# SCH_laptrinhoto_2025-12-04.net
KiCad netlist of a schematic drawn in EasyEDA
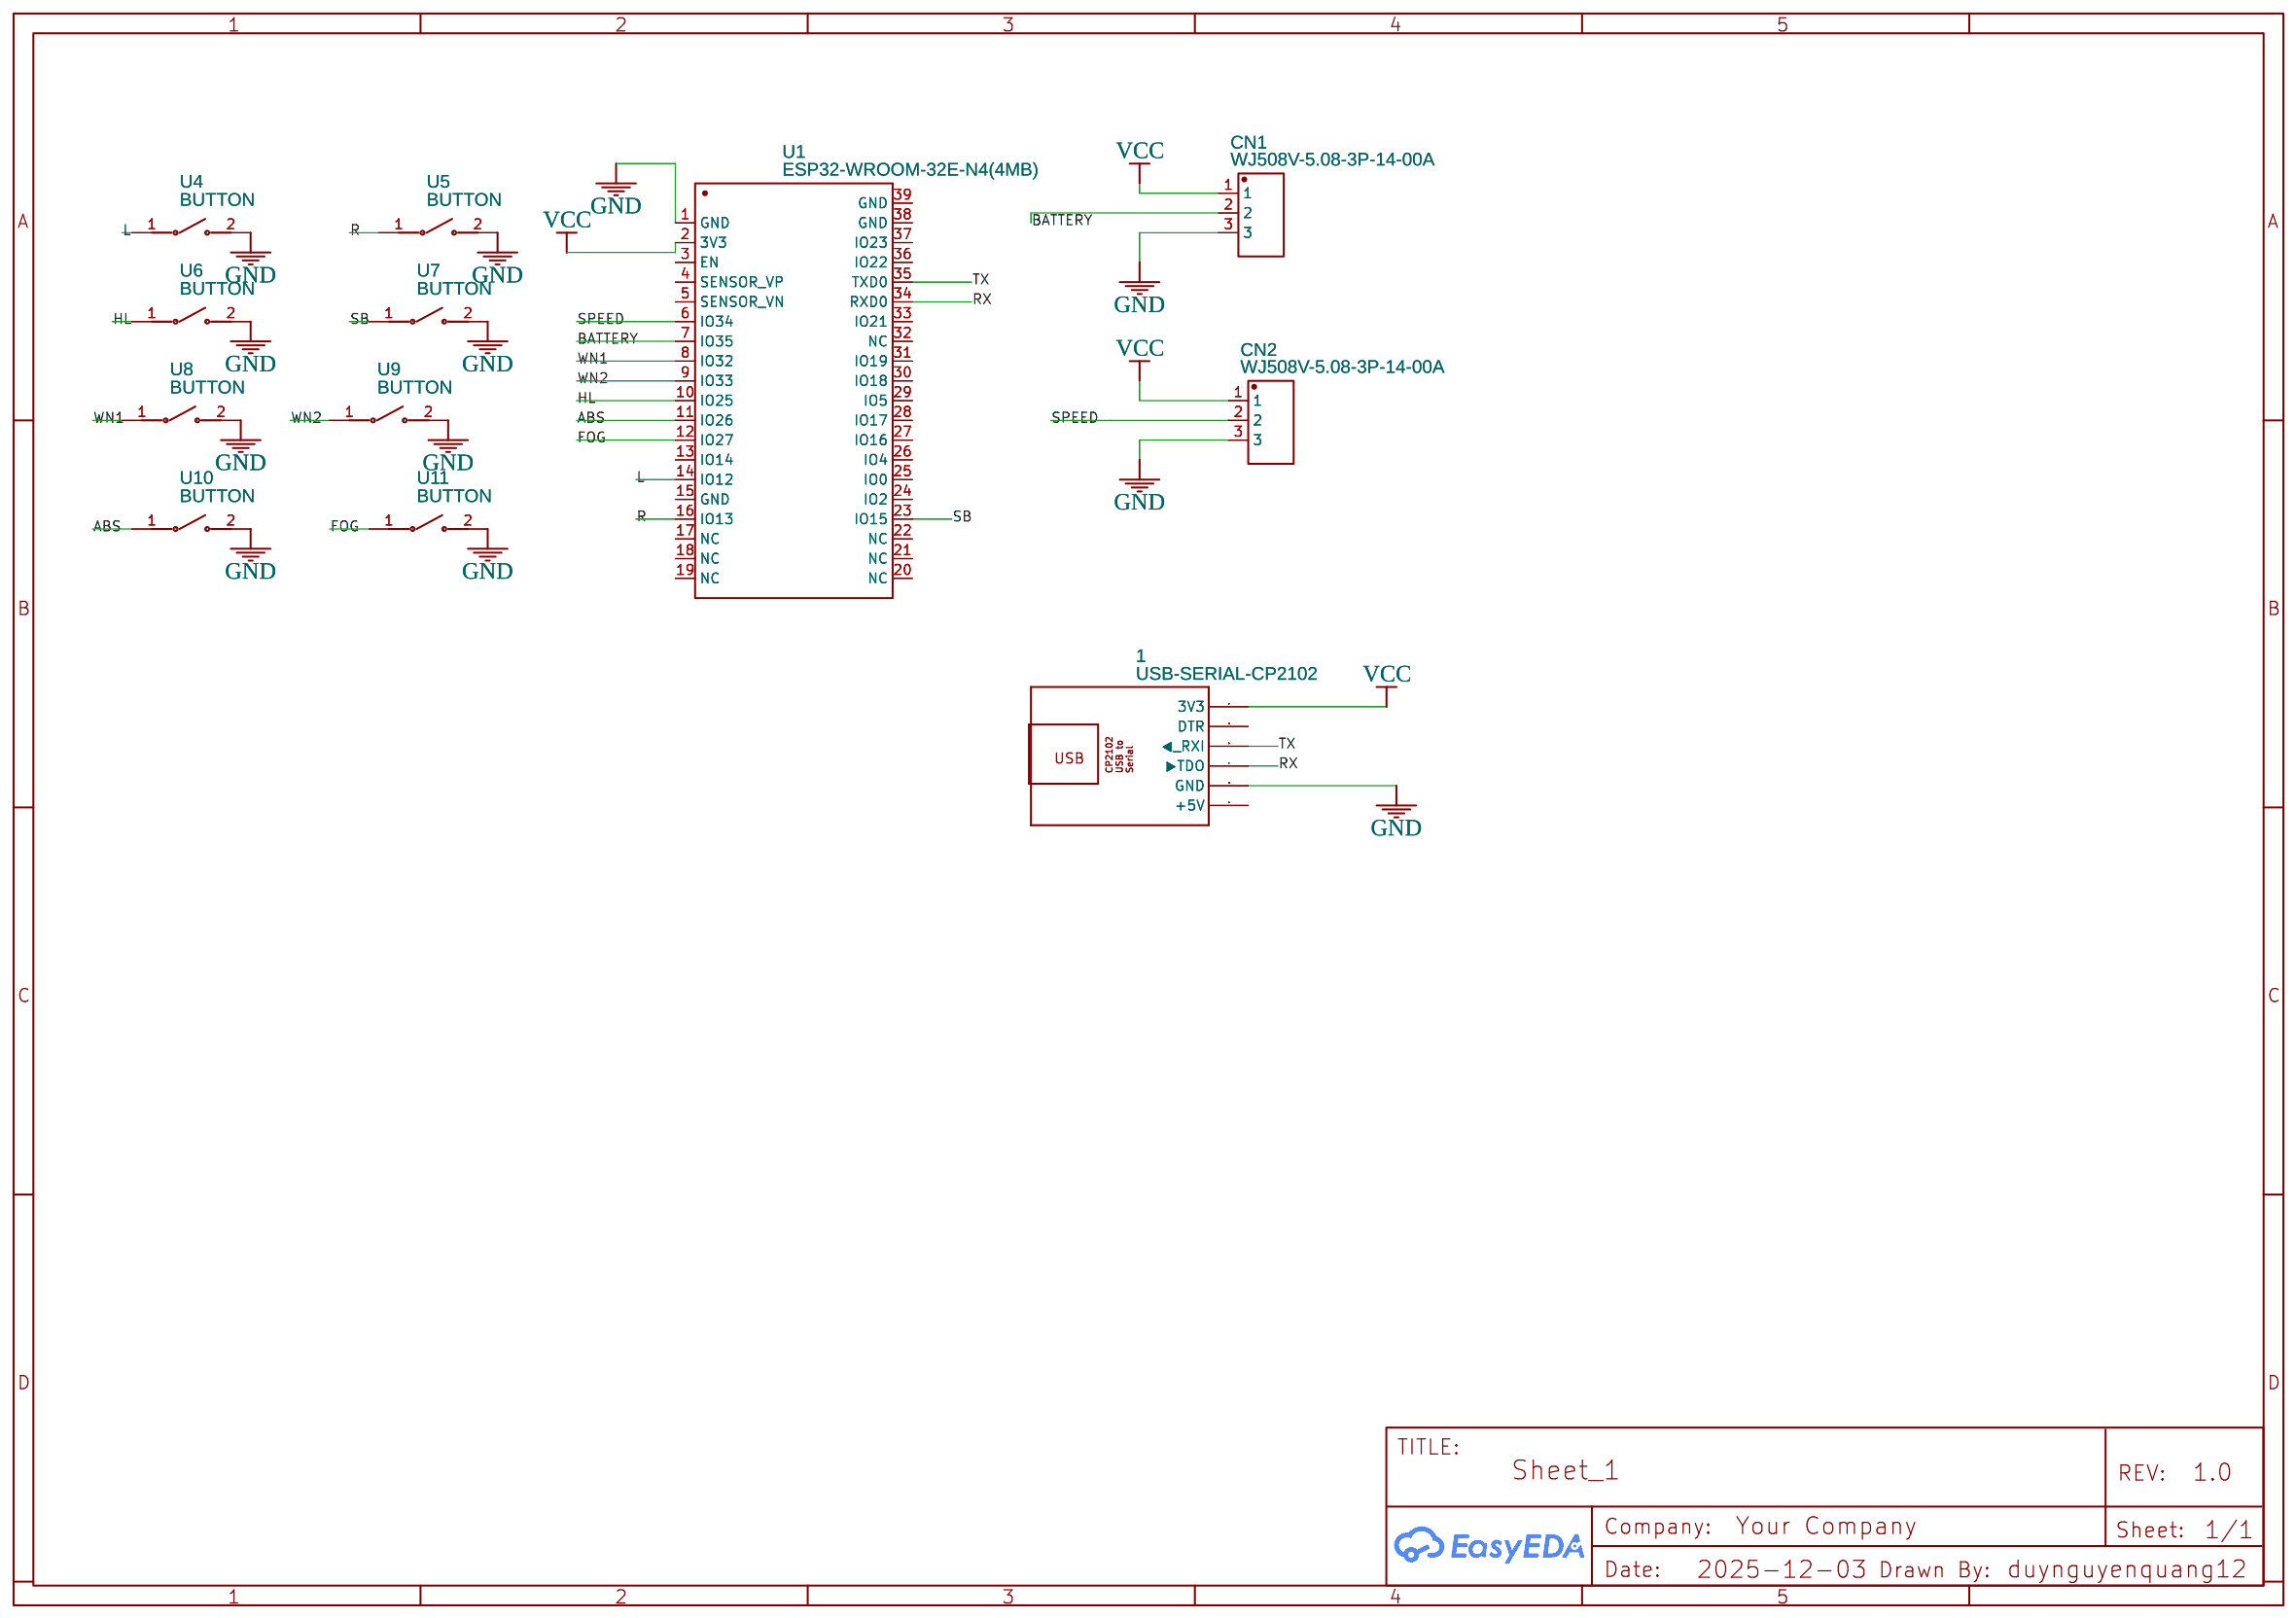
[diagram p0: schematic sheet]

(export (version "E")
  (design (tool "Eeschema 10.0.6"))
  (components
    (comp (ref "1") (value "USB-SERIAL-CP2102") (libsource (lib "") (part "USB-SERIAL-CP2102")))
    (comp (ref "CN1")
      (value "WJ508V-5.08-3P-14-00A")
      (fields (field (name "Manufacturer") "ReliaPro"))
      (libsource (lib "") (part "WJ508V-5.08-3P-14-00A"))
    )
    (comp (ref "CN2")
      (value "WJ508V-5.08-3P-14-00A")
      (fields (field (name "Manufacturer") "ReliaPro"))
      (libsource (lib "") (part "WJ508V-5.08-3P-14-00A"))
    )
    (comp (ref "U1") (value "ESP32-WROOM-32E-N4(4MB)") (libsource (lib "") (part "ESP32-WROOM-32E-N4(4MB)")))
    (comp (ref "U4") (value "BUTTON") (libsource (lib "") (part "BUTTON")))
    (comp (ref "U5") (value "BUTTON") (libsource (lib "") (part "BUTTON")))
    (comp (ref "U6") (value "BUTTON") (libsource (lib "") (part "BUTTON")))
    (comp (ref "U7") (value "BUTTON") (libsource (lib "") (part "BUTTON")))
    (comp (ref "U8") (value "BUTTON") (libsource (lib "") (part "BUTTON")))
    (comp (ref "U9") (value "BUTTON") (libsource (lib "") (part "BUTTON")))
    (comp (ref "U10") (value "BUTTON") (libsource (lib "") (part "BUTTON")))
    (comp (ref "U11") (value "BUTTON") (libsource (lib "") (part "BUTTON")))
  )
  (nets
    (net (code "1") (name "/ABS") (class "Default")
      (node (ref "U1") (pin "11") (pinfunction "IO26_11") (pintype "unspecified"))
      (node (ref "U10") (pin "1") (pinfunction "1_1") (pintype "unspecified"))
    )
    (net (code "2") (name "/BATTERY") (class "Default")
      (node (ref "CN1") (pin "2") (pinfunction "2_2") (pintype "unspecified"))
      (node (ref "U1") (pin "7") (pinfunction "IO35_7") (pintype "unspecified"))
    )
    (net (code "3") (name "/FOG") (class "Default")
      (node (ref "U1") (pin "12") (pinfunction "IO27_12") (pintype "unspecified"))
      (node (ref "U11") (pin "1") (pinfunction "1_1") (pintype "unspecified"))
    )
    (net (code "4") (name "/HL") (class "Default")
      (node (ref "U1") (pin "10") (pinfunction "IO25_10") (pintype "unspecified"))
      (node (ref "U6") (pin "1") (pinfunction "1_1") (pintype "unspecified"))
    )
    (net (code "5") (name "/L") (class "Default")
      (node (ref "U1") (pin "14") (pinfunction "IO12_14") (pintype "unspecified"))
      (node (ref "U4") (pin "1") (pinfunction "1_1") (pintype "unspecified"))
    )
    (net (code "6") (name "/R") (class "Default")
      (node (ref "U1") (pin "16") (pinfunction "IO13_16") (pintype "unspecified"))
      (node (ref "U5") (pin "1") (pinfunction "1_1") (pintype "unspecified"))
    )
    (net (code "7") (name "/RX") (class "Default")
      (node (ref "1") (pin "4") (pinfunction "▶TDO_4") (pintype "bidirectional"))
      (node (ref "U1") (pin "34") (pinfunction "RXD0_34") (pintype "unspecified"))
    )
    (net (code "8") (name "/SB") (class "Default")
      (node (ref "U1") (pin "23") (pinfunction "IO15_23") (pintype "unspecified"))
      (node (ref "U7") (pin "1") (pinfunction "1_1") (pintype "unspecified"))
    )
    (net (code "9") (name "/SPEED") (class "Default")
      (node (ref "CN2") (pin "2") (pinfunction "2_2") (pintype "unspecified"))
      (node (ref "U1") (pin "6") (pinfunction "IO34_6") (pintype "unspecified"))
    )
    (net (code "10") (name "/TX") (class "Default")
      (node (ref "1") (pin "3") (pinfunction "◀_RXI_3") (pintype "bidirectional"))
      (node (ref "U1") (pin "35") (pinfunction "TXD0_35") (pintype "unspecified"))
    )
    (net (code "11") (name "/WN1") (class "Default")
      (node (ref "U1") (pin "8") (pinfunction "IO32_8") (pintype "unspecified"))
      (node (ref "U8") (pin "1") (pinfunction "1_1") (pintype "unspecified"))
    )
    (net (code "12") (name "/WN2") (class "Default")
      (node (ref "U1") (pin "9") (pinfunction "IO33_9") (pintype "unspecified"))
      (node (ref "U9") (pin "1") (pinfunction "1_1") (pintype "unspecified"))
    )
    (net (code "13") (name "GND") (class "Default")
      (node (ref "1") (pin "5") (pinfunction "GND_5") (pintype "bidirectional"))
      (node (ref "CN1") (pin "3") (pinfunction "3_3") (pintype "unspecified"))
      (node (ref "CN2") (pin "3") (pinfunction "3_3") (pintype "unspecified"))
      (node (ref "U1") (pin "1") (pinfunction "GND_1") (pintype "unspecified"))
      (node (ref "U10") (pin "2") (pinfunction "2_2") (pintype "unspecified"))
      (node (ref "U11") (pin "2") (pinfunction "2_2") (pintype "unspecified"))
      (node (ref "U4") (pin "2") (pinfunction "2_2") (pintype "unspecified"))
      (node (ref "U5") (pin "2") (pinfunction "2_2") (pintype "unspecified"))
      (node (ref "U6") (pin "2") (pinfunction "2_2") (pintype "unspecified"))
      (node (ref "U7") (pin "2") (pinfunction "2_2") (pintype "unspecified"))
      (node (ref "U8") (pin "2") (pinfunction "2_2") (pintype "unspecified"))
      (node (ref "U9") (pin "2") (pinfunction "2_2") (pintype "unspecified"))
    )
    (net (code "14") (name "VCC") (class "Default")
      (node (ref "1") (pin "1") (pinfunction "3V3_1") (pintype "bidirectional"))
      (node (ref "CN1") (pin "1") (pinfunction "1_1") (pintype "unspecified"))
      (node (ref "CN2") (pin "1") (pinfunction "1_1") (pintype "unspecified"))
      (node (ref "U1") (pin "2") (pinfunction "3V3_2") (pintype "unspecified"))
    )
    (net (code "15") (name "unconnected-(1-+5V-Pad6)") (class "Default")
      (node (ref "1") (pin "6") (pinfunction "+5V_6") (pintype "bidirectional"))
    )
    (net (code "16") (name "unconnected-(1-DTR-Pad2)") (class "Default")
      (node (ref "1") (pin "2") (pinfunction "DTR_2") (pintype "bidirectional"))
    )
    (net (code "17") (name "unconnected-(U1-EN-Pad3)") (class "Default")
      (node (ref "U1") (pin "3") (pinfunction "EN_3") (pintype "unspecified"))
    )
    (net (code "18") (name "unconnected-(U1-GND-Pad15)") (class "Default")
      (node (ref "U1") (pin "15") (pinfunction "GND_15") (pintype "unspecified"))
    )
    (net (code "19") (name "unconnected-(U1-GND-Pad38)") (class "Default")
      (node (ref "U1") (pin "38") (pinfunction "GND_38") (pintype "unspecified"))
    )
    (net (code "20") (name "unconnected-(U1-GND-Pad39)") (class "Default")
      (node (ref "U1") (pin "39") (pinfunction "GND_39") (pintype "unspecified"))
    )
    (net (code "21") (name "unconnected-(U1-IO0-Pad25)") (class "Default")
      (node (ref "U1") (pin "25") (pinfunction "IO0_25") (pintype "unspecified"))
    )
    (net (code "22") (name "unconnected-(U1-IO2-Pad24)") (class "Default")
      (node (ref "U1") (pin "24") (pinfunction "IO2_24") (pintype "unspecified"))
    )
    (net (code "23") (name "unconnected-(U1-IO4-Pad26)") (class "Default")
      (node (ref "U1") (pin "26") (pinfunction "IO4_26") (pintype "unspecified"))
    )
    (net (code "24") (name "unconnected-(U1-IO5-Pad29)") (class "Default")
      (node (ref "U1") (pin "29") (pinfunction "IO5_29") (pintype "unspecified"))
    )
    (net (code "25") (name "unconnected-(U1-IO14-Pad13)") (class "Default")
      (node (ref "U1") (pin "13") (pinfunction "IO14_13") (pintype "unspecified"))
    )
    (net (code "26") (name "unconnected-(U1-IO16-Pad27)") (class "Default")
      (node (ref "U1") (pin "27") (pinfunction "IO16_27") (pintype "unspecified"))
    )
    (net (code "27") (name "unconnected-(U1-IO17-Pad28)") (class "Default")
      (node (ref "U1") (pin "28") (pinfunction "IO17_28") (pintype "unspecified"))
    )
    (net (code "28") (name "unconnected-(U1-IO18-Pad30)") (class "Default")
      (node (ref "U1") (pin "30") (pinfunction "IO18_30") (pintype "unspecified"))
    )
    (net (code "29") (name "unconnected-(U1-IO19-Pad31)") (class "Default")
      (node (ref "U1") (pin "31") (pinfunction "IO19_31") (pintype "unspecified"))
    )
    (net (code "30") (name "unconnected-(U1-IO21-Pad33)") (class "Default")
      (node (ref "U1") (pin "33") (pinfunction "IO21_33") (pintype "unspecified"))
    )
    (net (code "31") (name "unconnected-(U1-IO22-Pad36)") (class "Default")
      (node (ref "U1") (pin "36") (pinfunction "IO22_36") (pintype "unspecified"))
    )
    (net (code "32") (name "unconnected-(U1-IO23-Pad37)") (class "Default")
      (node (ref "U1") (pin "37") (pinfunction "IO23_37") (pintype "unspecified"))
    )
    (net (code "33") (name "unconnected-(U1-NC-Pad17)") (class "Default")
      (node (ref "U1") (pin "17") (pinfunction "NC_17") (pintype "unspecified"))
    )
    (net (code "34") (name "unconnected-(U1-NC-Pad18)") (class "Default")
      (node (ref "U1") (pin "18") (pinfunction "NC_18") (pintype "unspecified"))
    )
    (net (code "35") (name "unconnected-(U1-NC-Pad19)") (class "Default")
      (node (ref "U1") (pin "19") (pinfunction "NC_19") (pintype "unspecified"))
    )
    (net (code "36") (name "unconnected-(U1-NC-Pad20)") (class "Default")
      (node (ref "U1") (pin "20") (pinfunction "NC_20") (pintype "unspecified"))
    )
    (net (code "37") (name "unconnected-(U1-NC-Pad21)") (class "Default")
      (node (ref "U1") (pin "21") (pinfunction "NC_21") (pintype "unspecified"))
    )
    (net (code "38") (name "unconnected-(U1-NC-Pad22)") (class "Default")
      (node (ref "U1") (pin "22") (pinfunction "NC_22") (pintype "unspecified"))
    )
    (net (code "39") (name "unconnected-(U1-NC-Pad32)") (class "Default")
      (node (ref "U1") (pin "32") (pinfunction "NC_32") (pintype "unspecified"))
    )
    (net (code "40") (name "unconnected-(U1-SENSOR_VN-Pad5)") (class "Default")
      (node (ref "U1") (pin "5") (pinfunction "SENSOR_VN_5") (pintype "unspecified"))
    )
    (net (code "41") (name "unconnected-(U1-SENSOR_VP-Pad4)") (class "Default")
      (node (ref "U1") (pin "4") (pinfunction "SENSOR_VP_4") (pintype "unspecified"))
    )
  )
)
